# Valdis.net
KiCad netlist of a schematic drawn in Altium Designer
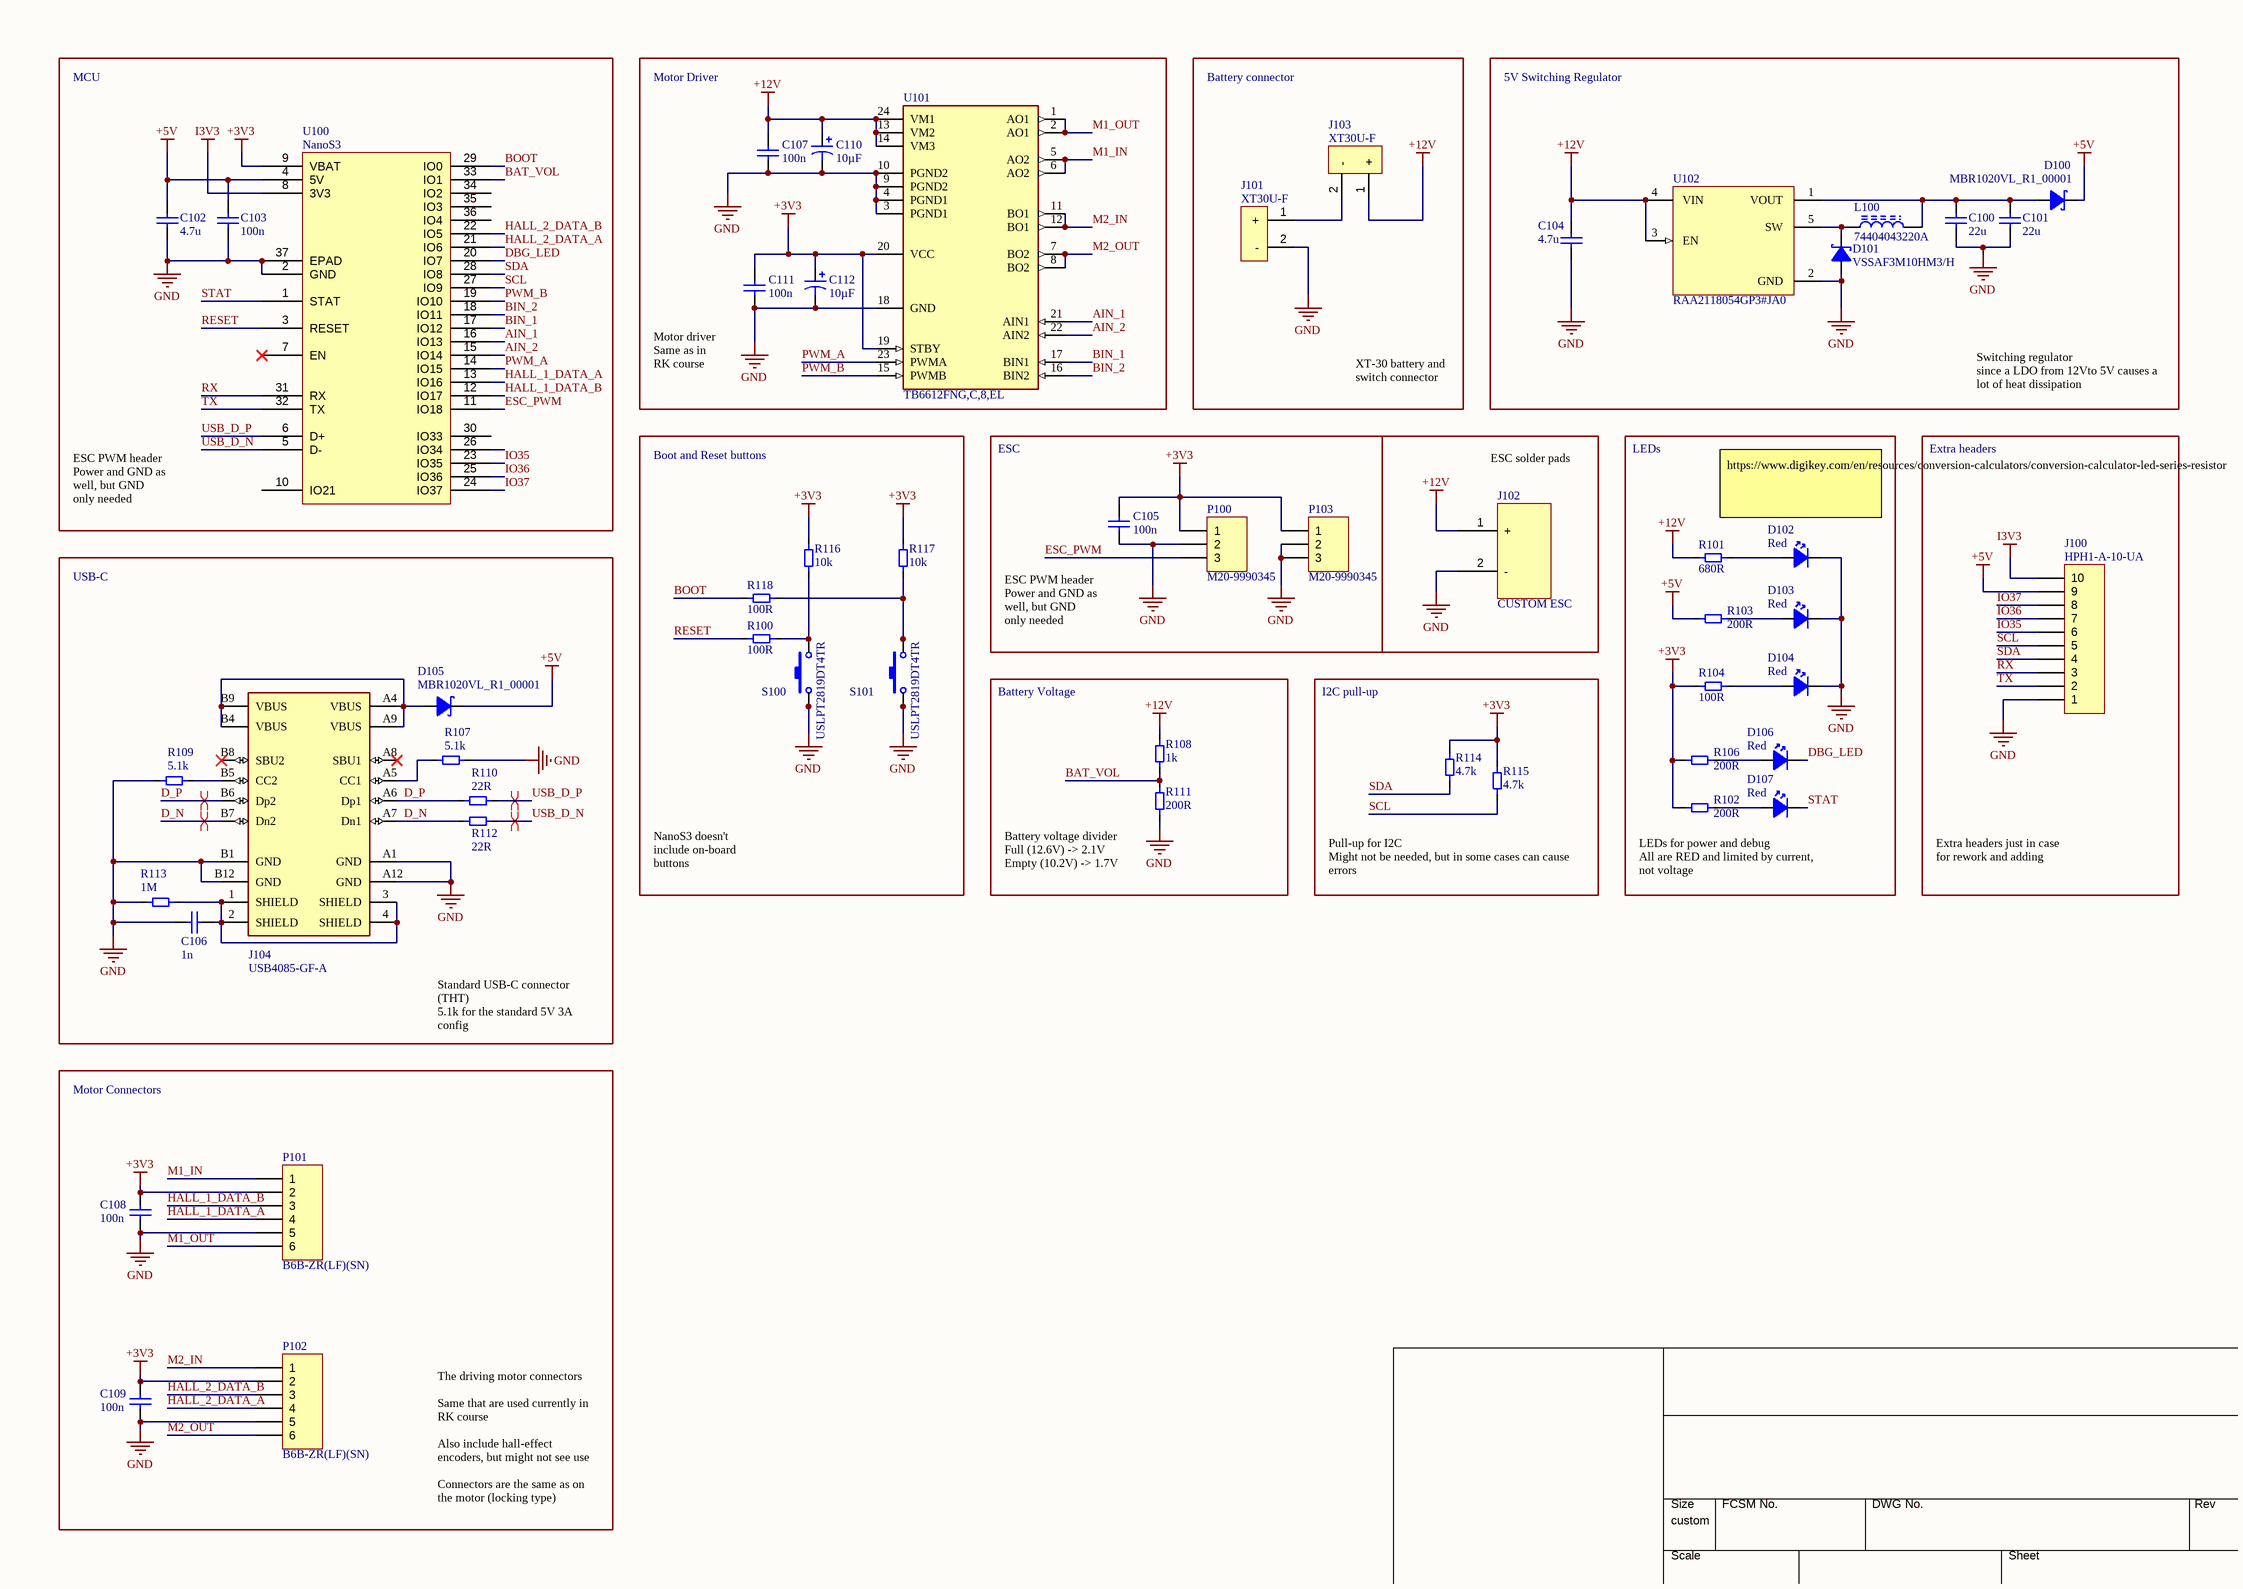
[diagram p0: Valdis.SchDoc]

(export (version "E")
  (design (tool "Eeschema 10.0.6"))
  (components
    (comp (ref "C100")
      (value "22u")
      (footprint "MLCC_1206_M")
      (description "MLCC, 1206, 22u, 10%, 16V, X5R")
      (fields (field (name "MANUFACTURER") "Any") (field (name "VOLTAGE") "16V"))
      (libsource (lib "Krakul Vault") (part "CAPACITOR_NONPOL_IEC"))
    )
    (comp (ref "C101")
      (value "22u")
      (footprint "MLCC_1206_M")
      (description "MLCC, 1206, 22u, 10%, 16V, X5R")
      (fields (field (name "MANUFACTURER") "Any") (field (name "VOLTAGE") "16V"))
      (libsource (lib "Krakul Vault") (part "CAPACITOR_NONPOL_IEC"))
    )
    (comp (ref "C102")
      (value "4.7u")
      (footprint "MLCC_0805_M")
      (description "MLCC, 0805, 4.7u, 10%, 50V, X5R")
      (fields (field (name "MANUFACTURER") "Any") (field (name "VOLTAGE") "50V"))
      (libsource (lib "Krakul Vault") (part "CAPACITOR_NONPOL_IEC"))
    )
    (comp (ref "C103")
      (value "100n")
      (footprint "MLCC_0603_M")
      (description "MLCC, 0603, 100n, 10%, 35V, X7R")
      (fields (field (name "MANUFACTURER") "Any") (field (name "VOLTAGE") "35V"))
      (libsource (lib "Krakul Vault") (part "CAPACITOR_NONPOL_IEC"))
    )
    (comp (ref "C104")
      (value "4.7u")
      (footprint "MLCC_1206_M")
      (description "MLCC, 1206, 4.7u, 10%, 35V, X5R")
      (fields (field (name "VOLTAGE") "35V") (field (name "TOLERANCE") "10%"))
      (libsource (lib "Krakul Vault") (part "CAPACITOR_NONPOL_IEC"))
    )
    (comp (ref "C105")
      (value "100n")
      (footprint "MLCC_0603_M")
      (description "MLCC, 0603, 100n, 10%, 50V, X7R")
      (fields (field (name "VOLTAGE") "50V") (field (name "TOLERANCE") "10%"))
      (libsource (lib "Krakul Vault") (part "CAPACITOR_NONPOL_IEC"))
    )
    (comp (ref "C106")
      (value "1n")
      (footprint "MLCC_0603_M")
      (description "MLCC, 0603, 1n, 10%, 50V, X7R")
      (fields (field (name "MANUFACTURER") "Any") (field (name "VOLTAGE") "50V"))
      (libsource (lib "Krakul Vault") (part "CAPACITOR_NONPOL_IEC"))
    )
    (comp (ref "C107")
      (value "100n")
      (footprint "MLCC_0603_M")
      (description "MLCC, 0603, 100n, 10%, 50V, X7R")
      (fields (field (name "VOLTAGE") "50V") (field (name "TOLERANCE") "10%"))
      (libsource (lib "Krakul Vault") (part "CAPACITOR_NONPOL_IEC"))
    )
    (comp (ref "C108")
      (value "100n")
      (footprint "MLCC_0603_M")
      (description "MLCC, 0603, 100n, 10%, 35V, X7R")
      (fields (field (name "MANUFACTURER") "Any") (field (name "VOLTAGE") "35V"))
      (libsource (lib "Krakul Vault") (part "CAPACITOR_NONPOL_IEC"))
    )
    (comp (ref "C109")
      (value "100n")
      (footprint "MLCC_0603_M")
      (description "MLCC, 0603, 100n, 10%, 35V, X7R")
      (fields (field (name "MANUFACTURER") "Any") (field (name "VOLTAGE") "35V"))
      (libsource (lib "Krakul Vault") (part "CAPACITOR_NONPOL_IEC"))
    )
    (comp (ref "C110")
      (value "10µF")
      (footprint "593D106X9025C2TE3-Footprint-1")
      (description "10UF Solid MNO2 Tantalum Electrolytic Capacitor, 25 V DC +/-10%, T495 Series")
      (fields (field (name "MANUFACTURER") "Any") (field (name "PART NUMBER") "T495B106K025ATE750"))
      (libsource (lib "Krakul Vault") (part "GENERIC ELECTROLYTIC CAP"))
    )
    (comp (ref "C111")
      (value "100n")
      (footprint "MLCC_0603_M")
      (description "MLCC, 0603, 100n, 10%, 50V, X7R")
      (fields (field (name "VOLTAGE") "50V") (field (name "TOLERANCE") "10%"))
      (libsource (lib "Krakul Vault") (part "CAPACITOR_NONPOL_IEC"))
    )
    (comp (ref "C112")
      (value "10µF")
      (footprint "593D106X9025C2TE3-Footprint-1")
      (description "10UF Solid MNO2 Tantalum Electrolytic Capacitor, 25 V DC +/-10%, T495 Series")
      (fields (field (name "MANUFACTURER") "Any") (field (name "PART NUMBER") "T495B106K025ATE750"))
      (libsource (lib "Krakul Vault") (part "GENERIC ELECTROLYTIC CAP"))
    )
    (comp (ref "D100")
      (value "MBR1020VL_R1_00001")
      (footprint "FP-MBR1020VL_R1_00001-MFG")
      (description "Rectifier Diode, Schottky, 1 Phase, 1 Element, 1A, 20V V(RRM), Silicon")
      (fields (field (name "MANUFACTURER") "Panjit"))
      (libsource (lib "Krakul Vault") (part "Schottky generic 2 pins"))
    )
    (comp (ref "D101")
      (value "VSSAF3M10HM3/H")
      (footprint "VSSAF3M10HM3_H-Footprint-1")
      (description "Rectifier Diode, Schottky, 1 Phase, 1 Element, 2.3A, 100V V(RRM), Silicon, DO-221AC")
      (libsource (lib "Krakul Vault") (part "Schottky generic 2 pins"))
    )
    (comp (ref "D102")
      (value "Red")
      (footprint "0603 RED LED")
      (description "Generic red 0603 LED")
      (fields (field (name "PART NUMBER") "Any Red 0603 LED") (field (name "MANUFACTURER") "Any"))
      (libsource (lib "Krakul Vault") (part "LED generic"))
    )
    (comp (ref "D103")
      (value "Red")
      (footprint "0603 RED LED")
      (description "Generic red 0603 LED")
      (fields (field (name "PART NUMBER") "Any Red 0603 LED") (field (name "MANUFACTURER") "Any"))
      (libsource (lib "Krakul Vault") (part "LED generic"))
    )
    (comp (ref "D104")
      (value "Red")
      (footprint "0603 RED LED")
      (description "Generic red 0603 LED")
      (fields (field (name "PART NUMBER") "Any Red 0603 LED") (field (name "MANUFACTURER") "Any"))
      (libsource (lib "Krakul Vault") (part "LED generic"))
    )
    (comp (ref "D105")
      (value "MBR1020VL_R1_00001")
      (footprint "FP-MBR1020VL_R1_00001-MFG")
      (description "Rectifier Diode, Schottky, 1 Phase, 1 Element, 1A, 20V V(RRM), Silicon")
      (fields (field (name "MANUFACTURER") "Panjit"))
      (libsource (lib "Krakul Vault") (part "Schottky generic 2 pins"))
    )
    (comp (ref "D106")
      (value "Red")
      (footprint "0603 RED LED")
      (description "Generic red 0603 LED")
      (fields (field (name "PART NUMBER") "Any Red 0603 LED") (field (name "MANUFACTURER") "Any"))
      (libsource (lib "Krakul Vault") (part "LED generic"))
    )
    (comp (ref "D107")
      (value "Red")
      (footprint "0603 RED LED")
      (description "Generic red 0603 LED")
      (fields (field (name "PART NUMBER") "Any Red 0603 LED") (field (name "MANUFACTURER") "Any"))
      (libsource (lib "Krakul Vault") (part "LED generic"))
    )
    (comp (ref "J100")
      (value "HPH1-A-10-UA")
      (footprint "HPH1-A-10-UA")
      (description "Conn Unshrouded Header HDR 10 POS 1.27mm Solder ST Top Entry Thru-Hole")
      (fields (field (name "MANUFACTURER") "Adam Tech"))
      (libsource (lib "Krakul Vault") (part "Header_Male_1R_10P"))
    )
    (comp (ref "J101")
      (value "XT30U-F")
      (footprint "XT30U-F")
      (description "Power Connector")
      (fields (field (name "MANUFACTURER") "AMASS"))
      (libsource (lib "Krakul Vault") (part "XT30U-F-Symbol-1"))
    )
    (comp (ref "J102")
      (value "CUSTOM ESC")
      (footprint "CUSTOM ESC-Footprint-1")
      (description "Custom ESC pinout")
      (fields (field (name "MANUFACTURER") "None"))
      (libsource (lib "Krakul Vault") (part "CUSTOM ESC"))
    )
    (comp (ref "J103")
      (value "XT30U-F")
      (footprint "XT30U-F")
      (description "Power Connector")
      (fields (field (name "MANUFACTURER") "AMASS"))
      (libsource (lib "") (part "XT30U-F-Symbol-1_1"))
    )
    (comp (ref "J104")
      (value "USB4085-GF-A")
      (footprint "FP-USB4085-GF-A-MFG")
      (description "USB Connector, 16 Contact(s), Female, Right Angle, Solder Terminal, Locking, Receptacle")
      (fields (field (name "MANUFACTURER") "GCT") (field (name "PART NUMBER") "USB4800-03-A"))
      (libsource (lib "Krakul Vault") (part "USB4085-GF-A"))
    )
    (comp (ref "L100")
      (value "74404043220A")
      (footprint "WE-LQS_4025")
      (description "General Purpose Inductor, 22uH, 20%, 1 Element, Nickel-zinc Ferrite-Core, SMD, 1616")
      (fields (field (name "MANUFACTURER") "Wurth Elektronik"))
      (libsource (lib "Krakul Vault") (part "INDUCTOR_SHIELDED"))
    )
    (comp (ref "P100")
      (value "M20-9990345")
      (footprint "3Pos Pin Header")
      (description "Connector Header Through Hole 3 position 0.100\" (2.54mm)")
      (fields (field (name "MANUFACTURER") "Harwin Inc."))
      (libsource (lib "Krakul Vault") (part "3 pin header"))
    )
    (comp (ref "P101")
      (value "B6B-ZR(LF)(SN)")
      (footprint "FP-B6B-ZR-SM4-TF_LF_SN-MFG")
      (description "Header for PCB; pitch 1.50mm; 6-contacts; THT; male; top entry; 50V/1A")
      (fields (field (name "MANUFACTURER") "JST Sales America Inc.") (field (name "PART NUMBER") "B6B-ZR"))
      (libsource (lib "Krakul Vault") (part "6 pin header"))
    )
    (comp (ref "P102")
      (value "B6B-ZR(LF)(SN)")
      (footprint "FP-B6B-ZR-SM4-TF_LF_SN-MFG")
      (description "Header for PCB; pitch 1.50mm; 6-contacts; THT; male; top entry; 50V/1A")
      (fields (field (name "MANUFACTURER") "JST Sales America Inc.") (field (name "PART NUMBER") "B6B-ZR"))
      (libsource (lib "Krakul Vault") (part "6 pin header"))
    )
    (comp (ref "P103")
      (value "M20-9990345")
      (footprint "3Pos Pin Header")
      (description "Connector Header Through Hole 3 position 0.100\" (2.54mm)")
      (fields (field (name "MANUFACTURER") "Harwin Inc."))
      (libsource (lib "Krakul Vault") (part "3 pin header"))
    )
    (comp (ref "R100")
      (value "100R")
      (footprint "Resistor_0603_M")
      (description "Resistor, 0603, 100R, 1%, 1/10W")
      (fields (field (name "POWER") "100mW") (field (name "MANUFACTURER") "Any"))
      (libsource (lib "Krakul Vault") (part "RESISTOR_GENERIC_IEC"))
    )
    (comp (ref "R101")
      (value "680R")
      (footprint "Resistor_0603_M")
      (description "Resistor, 0603, 680R, 1%, 1/10W")
      (fields (field (name "POWER") "100mW") (field (name "TOLERANCE") "1%"))
      (libsource (lib "Krakul Vault") (part "RESISTOR_GENERIC_IEC"))
    )
    (comp (ref "R102")
      (value "200R")
      (footprint "Resistor_0603_M")
      (description "Resistor, 0603, 200R, 1%, 1/10W")
      (fields (field (name "TOLERANCE") "1%") (field (name "POWER") "100mW"))
      (libsource (lib "Krakul Vault") (part "RESISTOR_GENERIC_IEC"))
    )
    (comp (ref "R103")
      (value "200R")
      (footprint "Resistor_0603_M")
      (description "Resistor, 0603, 200R, 1%, 1/10W")
      (fields (field (name "TOLERANCE") "1%") (field (name "POWER") "100mW"))
      (libsource (lib "Krakul Vault") (part "RESISTOR_GENERIC_IEC"))
    )
    (comp (ref "R104")
      (value "100R")
      (footprint "Resistor_0603_M")
      (description "Resistor, 0603, 100R, ≤5%, ≥1/16W")
      (fields (field (name "MANUFACTURER") "Any"))
      (libsource (lib "Krakul Vault") (part "RESISTOR_GENERIC_IEC"))
    )
    (comp (ref "R106")
      (value "200R")
      (footprint "Resistor_0603_M")
      (description "Resistor, 0603, 200R, 1%, 1/10W")
      (fields (field (name "TOLERANCE") "1%") (field (name "POWER") "100mW"))
      (libsource (lib "Krakul Vault") (part "RESISTOR_GENERIC_IEC"))
    )
    (comp (ref "R107")
      (value "5.1k")
      (footprint "Resistor_0603_M")
      (description "Resistor, 0603, 5.1k, 1%, 1/10W")
      (fields (field (name "POWER") "100mW") (field (name "MANUFACTURER") "Any"))
      (libsource (lib "Krakul Vault") (part "RESISTOR_GENERIC_IEC"))
    )
    (comp (ref "R108")
      (value "1k")
      (footprint "Resistor_0603_M")
      (description "Resistor, 0603, 1k, 0.1%, 1/16W")
      (fields (field (name "MANUFACTURER") "Any"))
      (libsource (lib "Krakul Vault") (part "RESISTOR_GENERIC_IEC"))
    )
    (comp (ref "R109")
      (value "5.1k")
      (footprint "Resistor_0603_M")
      (description "Resistor, 0603, 5.1k, 1%, 1/10W")
      (fields (field (name "POWER") "100mW") (field (name "MANUFACTURER") "Any"))
      (libsource (lib "Krakul Vault") (part "RESISTOR_GENERIC_IEC"))
    )
    (comp (ref "R110")
      (value "22R")
      (footprint "Resistor_0603_M")
      (description "Resistor, 0603, 22R, 1%, 1/10W")
      (fields (field (name "TOLERANCE") "1%") (field (name "MANUFACTURER") "Any"))
      (libsource (lib "Krakul Vault") (part "RESISTOR_GENERIC_IEC"))
    )
    (comp (ref "R111")
      (value "200R")
      (footprint "Resistor_0603_M")
      (description "Resistor, 0603, 220R, 1%, 1/10W")
      (fields (field (name "TOLERANCE") "1%") (field (name "MANUFACTURER") "Any"))
      (libsource (lib "Krakul Vault") (part "RESISTOR_GENERIC_IEC"))
    )
    (comp (ref "R112")
      (value "22R")
      (footprint "Resistor_0603_M")
      (description "Resistor, 0603, 22R, 1%, 1/10W")
      (fields (field (name "TOLERANCE") "1%") (field (name "MANUFACTURER") "Any"))
      (libsource (lib "Krakul Vault") (part "RESISTOR_GENERIC_IEC"))
    )
    (comp (ref "R113")
      (value "1M")
      (footprint "Resistor_1206_M")
      (description "Resistor, 1206, 1M, 1%, 1/4W")
      (fields (field (name "MANUFACTURER") "Any"))
      (libsource (lib "Krakul Vault") (part "RESISTOR_GENERIC_IEC"))
    )
    (comp (ref "R114")
      (value "4.7k")
      (footprint "Resistor_0603_M")
      (description "Resistor, 0603, 4.7k, 1%, 1/10W")
      (fields (field (name "MANUFACTURER") "Any") (field (name "POWER") "100mW"))
      (libsource (lib "Krakul Vault") (part "RESISTOR_GENERIC_IEC"))
    )
    (comp (ref "R115")
      (value "4.7k")
      (footprint "Resistor_0603_M")
      (description "Resistor, 0603, 4.7k, 1%, 1/10W")
      (fields (field (name "MANUFACTURER") "Any") (field (name "POWER") "100mW"))
      (libsource (lib "Krakul Vault") (part "RESISTOR_GENERIC_IEC"))
    )
    (comp (ref "R116")
      (value "10k")
      (footprint "Resistor_0603_M")
      (description "Resistor, 0603, 10k, 1%, 1/10W")
      (fields (field (name "MANUFACTURER") "Any") (field (name "TOLERANCE") "1%"))
      (libsource (lib "Krakul Vault") (part "RESISTOR_GENERIC_IEC"))
    )
    (comp (ref "R117")
      (value "10k")
      (footprint "Resistor_0603_M")
      (description "Resistor, 0603, 10k, 1%, 1/10W")
      (fields (field (name "MANUFACTURER") "Any") (field (name "TOLERANCE") "1%"))
      (libsource (lib "Krakul Vault") (part "RESISTOR_GENERIC_IEC"))
    )
    (comp (ref "R118")
      (value "100R")
      (footprint "Resistor_0603_M")
      (description "Resistor, 0603, 100R, 1%, 1/10W")
      (fields (field (name "POWER") "100mW") (field (name "MANUFACTURER") "Any"))
      (libsource (lib "Krakul Vault") (part "RESISTOR_GENERIC_IEC"))
    )
    (comp (ref "S100")
      (value "USLPT2819DT4TR")
      (footprint "USLPT2819DT4TR-Footprint-1")
      (description "Keypad Switch, SPST, 0.05A, 1.96N, Solder Terminal, Panel Mount")
      (fields (field (name "MANUFACTURER") "TE Connectivity ALCOSWITCH Switches"))
      (libsource (lib "Krakul Vault") (part "Copy of Switch 4-pin"))
    )
    (comp (ref "S101")
      (value "USLPT2819DT4TR")
      (footprint "USLPT2819DT4TR-Footprint-1")
      (description "Keypad Switch, SPST, 0.05A, 1.96N, Solder Terminal, Panel Mount")
      (fields (field (name "MANUFACTURER") "TE Connectivity ALCOSWITCH Switches"))
      (libsource (lib "Krakul Vault") (part "Copy of Switch 4-pin"))
    )
    (comp (ref "U100")
      (value "NanoS3")
      (footprint "NanoS3")
      (description "Unexpected Maker's NanoS3 DevKit")
      (fields (field (name "MANUFACTURER") "Unexpected Maker"))
      (libsource (lib "Krakul Vault") (part "NanoS3"))
    )
    (comp (ref "U101")
      (value "TB6612FNG,C,8,EL")
      (footprint "FP-SSOP24-P-300-0_65A-MFG")
      (description "DC Motor Driver 2.7V to 5.5V 24-Pin SSOP Embossed T/R")
      (fields (field (name "MANUFACTURER") "Toshiba") (field (name "PART NUMBER") "TBG6612FNG"))
      (libsource (lib "Krakul Vault") (part "TBG6612FNG"))
    )
    (comp (ref "U102")
      (value "RAA2118054GP3#JA0")
      (footprint "P5_064B_MFG")
      (description "Switching Regulator, Current-mode, 0.3A, 230kHz Switching Freq-Max, PDSO5")
      (fields (field (name "MANUFACTURER") "Renesas / Intersil"))
      (libsource (lib "Krakul Vault") (part "04ef17e7ed04f306c00cc4b237f44d7"))
    )
  )
  (nets
    (net (code "1") (name "+3V3") (class "Default")
      (node (ref "C105") (pin "1") (pinfunction "1_1") (pintype "passive"))
      (node (ref "C108") (pin "2") (pinfunction "2_2") (pintype "passive"))
      (node (ref "C109") (pin "2") (pinfunction "2_2") (pintype "passive"))
      (node (ref "C111") (pin "1") (pinfunction "1_1") (pintype "passive"))
      (node (ref "C112") (pin "2") (pinfunction "2_2") (pintype "passive"))
      (node (ref "P100") (pin "1") (pinfunction "1_1") (pintype "passive"))
      (node (ref "P101") (pin "2") (pinfunction "2_2") (pintype "passive"))
      (node (ref "P102") (pin "2") (pinfunction "2_2") (pintype "passive"))
      (node (ref "P103") (pin "1") (pinfunction "1_1") (pintype "passive"))
      (node (ref "R102") (pin "1") (pinfunction "1_1") (pintype "passive"))
      (node (ref "R104") (pin "1") (pinfunction "1_1") (pintype "passive"))
      (node (ref "R106") (pin "1") (pinfunction "1_1") (pintype "passive"))
      (node (ref "R114") (pin "2") (pinfunction "2_2") (pintype "passive"))
      (node (ref "R115") (pin "2") (pinfunction "2_2") (pintype "passive"))
      (node (ref "R116") (pin "2") (pinfunction "2_2") (pintype "passive"))
      (node (ref "R117") (pin "2") (pinfunction "2_2") (pintype "passive"))
      (node (ref "U100") (pin "9") (pinfunction "VBAT_9") (pintype "passive"))
      (node (ref "U101") (pin "19") (pinfunction "STBY_19") (pintype "input"))
      (node (ref "U101") (pin "20") (pinfunction "VCC_20") (pintype "power_in"))
    )
    (net (code "2") (name "+5V") (class "Default")
      (node (ref "C102") (pin "2") (pinfunction "2_2") (pintype "passive"))
      (node (ref "C103") (pin "2") (pinfunction "2_2") (pintype "passive"))
      (node (ref "D100") (pin "1") (pinfunction "C_1") (pintype "passive"))
      (node (ref "D105") (pin "1") (pinfunction "C_1") (pintype "passive"))
      (node (ref "J100") (pin "9") (pinfunction "9_9") (pintype "passive"))
      (node (ref "R103") (pin "1") (pinfunction "1_1") (pintype "passive"))
      (node (ref "U100") (pin "4") (pinfunction "5V_4") (pintype "passive"))
    )
    (net (code "3") (name "+12V") (class "Default")
      (node (ref "C104") (pin "2") (pinfunction "2_2") (pintype "passive"))
      (node (ref "C107") (pin "1") (pinfunction "1_1") (pintype "passive"))
      (node (ref "C110") (pin "2") (pinfunction "2_2") (pintype "passive"))
      (node (ref "J102") (pin "1") (pinfunction "+_1") (pintype "passive"))
      (node (ref "J103") (pin "1") (pinfunction "+_1") (pintype "passive"))
      (node (ref "R101") (pin "2") (pinfunction "2_2") (pintype "passive"))
      (node (ref "R108") (pin "2") (pinfunction "2_2") (pintype "passive"))
      (node (ref "U101") (pin "13") (pinfunction "VM2_13") (pintype "power_in"))
      (node (ref "U101") (pin "14") (pinfunction "VM3_14") (pintype "power_in"))
      (node (ref "U101") (pin "24") (pinfunction "VM1_24") (pintype "power_in"))
      (node (ref "U102") (pin "3") (pinfunction "EN_3") (pintype "input"))
      (node (ref "U102") (pin "4") (pinfunction "VIN_4") (pintype "power_in"))
    )
    (net (code "4") (name "/AIN_1") (class "Default")
      (node (ref "U100") (pin "16") (pinfunction "IO13_16") (pintype "passive"))
      (node (ref "U101") (pin "21") (pinfunction "AIN1_21") (pintype "input"))
    )
    (net (code "5") (name "/AIN_2") (class "Default")
      (node (ref "U100") (pin "15") (pinfunction "IO14_15") (pintype "passive"))
      (node (ref "U101") (pin "22") (pinfunction "AIN2_22") (pintype "input"))
    )
    (net (code "6") (name "/BAT_VOL") (class "Default")
      (node (ref "R108") (pin "1") (pinfunction "1_1") (pintype "passive"))
      (node (ref "R111") (pin "2") (pinfunction "2_2") (pintype "passive"))
      (node (ref "U100") (pin "33") (pinfunction "IO1_33") (pintype "passive"))
    )
    (net (code "7") (name "/BIN_1") (class "Default")
      (node (ref "U100") (pin "17") (pinfunction "IO12_17") (pintype "passive"))
      (node (ref "U101") (pin "17") (pinfunction "BIN1_17") (pintype "input"))
    )
    (net (code "8") (name "/BIN_2") (class "Default")
      (node (ref "U100") (pin "18") (pinfunction "IO11_18") (pintype "passive"))
      (node (ref "U101") (pin "16") (pinfunction "BIN2_16") (pintype "input"))
    )
    (net (code "9") (name "/BOOT") (class "Default")
      (node (ref "R118") (pin "2") (pinfunction "2_2") (pintype "passive"))
      (node (ref "U100") (pin "29") (pinfunction "IO0_29") (pintype "passive"))
    )
    (net (code "10") (name "/DBG_LED") (class "Default")
      (node (ref "D106") (pin "1") (pinfunction "C_1") (pintype "passive"))
      (node (ref "U100") (pin "20") (pinfunction "IO7_20") (pintype "passive"))
    )
    (net (code "11") (name "/D_N") (class "Default")
      (node (ref "J104") (pin "A7") (pinfunction "Dn1_A7") (pintype "bidirectional"))
      (node (ref "J104") (pin "B7") (pinfunction "Dn2_B7") (pintype "bidirectional"))
      (node (ref "R112") (pin "1") (pinfunction "1_1") (pintype "passive"))
    )
    (net (code "12") (name "/D_P") (class "Default")
      (node (ref "J104") (pin "A6") (pinfunction "Dp1_A6") (pintype "bidirectional"))
      (node (ref "J104") (pin "B6") (pinfunction "Dp2_B6") (pintype "bidirectional"))
      (node (ref "R110") (pin "1") (pinfunction "1_1") (pintype "passive"))
    )
    (net (code "13") (name "/ESC_PWM") (class "Default")
      (node (ref "P100") (pin "3") (pinfunction "3_3") (pintype "passive"))
      (node (ref "U100") (pin "11") (pinfunction "IO18_11") (pintype "passive"))
    )
    (net (code "14") (name "/HALL_1_DATA_A") (class "Default")
      (node (ref "P101") (pin "4") (pinfunction "4_4") (pintype "passive"))
      (node (ref "U100") (pin "13") (pinfunction "IO16_13") (pintype "passive"))
    )
    (net (code "15") (name "/HALL_1_DATA_B") (class "Default")
      (node (ref "P101") (pin "3") (pinfunction "3_3") (pintype "passive"))
      (node (ref "U100") (pin "12") (pinfunction "IO17_12") (pintype "passive"))
    )
    (net (code "16") (name "/HALL_2_DATA_A") (class "Default")
      (node (ref "P102") (pin "4") (pinfunction "4_4") (pintype "passive"))
      (node (ref "U100") (pin "21") (pinfunction "IO6_21") (pintype "passive"))
    )
    (net (code "17") (name "/HALL_2_DATA_B") (class "Default")
      (node (ref "P102") (pin "3") (pinfunction "3_3") (pintype "passive"))
      (node (ref "U100") (pin "22") (pinfunction "IO5_22") (pintype "passive"))
    )
    (net (code "18") (name "/IO35") (class "Default")
      (node (ref "J100") (pin "6") (pinfunction "6_6") (pintype "passive"))
      (node (ref "U100") (pin "23") (pinfunction "IO35_23") (pintype "passive"))
    )
    (net (code "19") (name "/IO36") (class "Default")
      (node (ref "J100") (pin "7") (pinfunction "7_7") (pintype "passive"))
      (node (ref "U100") (pin "25") (pinfunction "IO36_25") (pintype "passive"))
    )
    (net (code "20") (name "/IO37") (class "Default")
      (node (ref "J100") (pin "8") (pinfunction "8_8") (pintype "passive"))
      (node (ref "U100") (pin "24") (pinfunction "IO37_24") (pintype "passive"))
    )
    (net (code "21") (name "/M1_IN") (class "Default")
      (node (ref "P101") (pin "1") (pinfunction "1_1") (pintype "passive"))
      (node (ref "U101") (pin "5") (pinfunction "AO2_5") (pintype "output"))
      (node (ref "U101") (pin "6") (pinfunction "AO2_6") (pintype "output"))
    )
    (net (code "22") (name "/M1_OUT") (class "Default")
      (node (ref "P101") (pin "6") (pinfunction "6_6") (pintype "passive"))
      (node (ref "U101") (pin "1") (pinfunction "AO1_1") (pintype "output"))
      (node (ref "U101") (pin "2") (pinfunction "AO1_2") (pintype "output"))
    )
    (net (code "23") (name "/M2_IN") (class "Default")
      (node (ref "P102") (pin "1") (pinfunction "1_1") (pintype "passive"))
      (node (ref "U101") (pin "11") (pinfunction "BO1_11") (pintype "output"))
      (node (ref "U101") (pin "12") (pinfunction "BO1_12") (pintype "output"))
    )
    (net (code "24") (name "/M2_OUT") (class "Default")
      (node (ref "P102") (pin "6") (pinfunction "6_6") (pintype "passive"))
      (node (ref "U101") (pin "7") (pinfunction "BO2_7") (pintype "output"))
      (node (ref "U101") (pin "8") (pinfunction "BO2_8") (pintype "output"))
    )
    (net (code "25") (name "/PWM_A") (class "Default")
      (node (ref "U100") (pin "14") (pinfunction "IO15_14") (pintype "passive"))
      (node (ref "U101") (pin "23") (pinfunction "PWMA_23") (pintype "input"))
    )
    (net (code "26") (name "/PWM_B") (class "Default")
      (node (ref "U100") (pin "19") (pinfunction "IO10_19") (pintype "passive"))
      (node (ref "U101") (pin "15") (pinfunction "PWMB_15") (pintype "input"))
    )
    (net (code "27") (name "/RESET") (class "Default")
      (node (ref "R100") (pin "2") (pinfunction "2_2") (pintype "passive"))
      (node (ref "U100") (pin "3") (pinfunction "RESET_3") (pintype "passive"))
    )
    (net (code "28") (name "/RX") (class "Default")
      (node (ref "J100") (pin "3") (pinfunction "3_3") (pintype "passive"))
      (node (ref "U100") (pin "31") (pinfunction "RX_31") (pintype "passive"))
    )
    (net (code "29") (name "/SCL") (class "Default")
      (node (ref "J100") (pin "5") (pinfunction "5_5") (pintype "passive"))
      (node (ref "R115") (pin "1") (pinfunction "1_1") (pintype "passive"))
      (node (ref "U100") (pin "27") (pinfunction "IO9_27") (pintype "passive"))
    )
    (net (code "30") (name "/SDA") (class "Default")
      (node (ref "J100") (pin "4") (pinfunction "4_4") (pintype "passive"))
      (node (ref "R114") (pin "1") (pinfunction "1_1") (pintype "passive"))
      (node (ref "U100") (pin "28") (pinfunction "IO8_28") (pintype "passive"))
    )
    (net (code "31") (name "/STAT") (class "Default")
      (node (ref "D107") (pin "1") (pinfunction "C_1") (pintype "passive"))
      (node (ref "U100") (pin "1") (pinfunction "STAT_1") (pintype "passive"))
    )
    (net (code "32") (name "/TX") (class "Default")
      (node (ref "J100") (pin "2") (pinfunction "2_2") (pintype "passive"))
      (node (ref "U100") (pin "32") (pinfunction "TX_32") (pintype "passive"))
    )
    (net (code "33") (name "/USB_D_N") (class "Default")
      (node (ref "R112") (pin "2") (pinfunction "2_2") (pintype "passive"))
      (node (ref "U100") (pin "5") (pinfunction "D-_5") (pintype "passive"))
    )
    (net (code "34") (name "/USB_D_P") (class "Default")
      (node (ref "R110") (pin "2") (pinfunction "2_2") (pintype "passive"))
      (node (ref "U100") (pin "6") (pinfunction "D+_6") (pintype "passive"))
    )
    (net (code "35") (name "GND") (class "Default")
      (node (ref "C100") (pin "1") (pinfunction "1_1") (pintype "passive"))
      (node (ref "C101") (pin "1") (pinfunction "1_1") (pintype "passive"))
      (node (ref "C102") (pin "1") (pinfunction "1_1") (pintype "passive"))
      (node (ref "C103") (pin "1") (pinfunction "1_1") (pintype "passive"))
      (node (ref "C104") (pin "1") (pinfunction "1_1") (pintype "passive"))
      (node (ref "C105") (pin "2") (pinfunction "2_2") (pintype "passive"))
      (node (ref "C106") (pin "2") (pinfunction "2_2") (pintype "passive"))
      (node (ref "C107") (pin "2") (pinfunction "2_2") (pintype "passive"))
      (node (ref "C108") (pin "1") (pinfunction "1_1") (pintype "passive"))
      (node (ref "C109") (pin "1") (pinfunction "1_1") (pintype "passive"))
      (node (ref "C110") (pin "1") (pinfunction "1_1") (pintype "passive"))
      (node (ref "C111") (pin "2") (pinfunction "2_2") (pintype "passive"))
      (node (ref "C112") (pin "1") (pinfunction "1_1") (pintype "passive"))
      (node (ref "D101") (pin "2") (pinfunction "A_2") (pintype "passive"))
      (node (ref "D102") (pin "1") (pinfunction "C_1") (pintype "passive"))
      (node (ref "D103") (pin "1") (pinfunction "C_1") (pintype "passive"))
      (node (ref "D104") (pin "1") (pinfunction "C_1") (pintype "passive"))
      (node (ref "J100") (pin "1") (pinfunction "1_1") (pintype "passive"))
      (node (ref "J101") (pin "2") (pinfunction "-_2") (pintype "passive"))
      (node (ref "J102") (pin "2") (pinfunction "-_2") (pintype "passive"))
      (node (ref "J104") (pin "A1") (pinfunction "GND_A1") (pintype "power_in"))
      (node (ref "J104") (pin "A12") (pinfunction "GND_A12") (pintype "power_in"))
      (node (ref "J104") (pin "B1") (pinfunction "GND_B1") (pintype "power_in"))
      (node (ref "J104") (pin "B12") (pinfunction "GND_B12") (pintype "power_in"))
      (node (ref "P100") (pin "2") (pinfunction "2_2") (pintype "passive"))
      (node (ref "P101") (pin "5") (pinfunction "5_5") (pintype "passive"))
      (node (ref "P102") (pin "5") (pinfunction "5_5") (pintype "passive"))
      (node (ref "P103") (pin "2") (pinfunction "2_2") (pintype "passive"))
      (node (ref "P103") (pin "3") (pinfunction "3_3") (pintype "passive"))
      (node (ref "R107") (pin "2") (pinfunction "2_2") (pintype "passive"))
      (node (ref "R109") (pin "1") (pinfunction "1_1") (pintype "passive"))
      (node (ref "R111") (pin "1") (pinfunction "1_1") (pintype "passive"))
      (node (ref "R113") (pin "2") (pinfunction "2_2") (pintype "passive"))
      (node (ref "S100") (pin "1") (pinfunction "1_1") (pintype "passive"))
      (node (ref "S100") (pin "2") (pinfunction "2_2") (pintype "passive"))
      (node (ref "S101") (pin "1") (pinfunction "1_1") (pintype "passive"))
      (node (ref "S101") (pin "2") (pinfunction "2_2") (pintype "passive"))
      (node (ref "U100") (pin "2") (pinfunction "GND_2") (pintype "passive"))
      (node (ref "U100") (pin "37") (pinfunction "EPAD_37") (pintype "passive"))
      (node (ref "U101") (pin "10") (pinfunction "PGND2_10") (pintype "power_in"))
      (node (ref "U101") (pin "18") (pinfunction "GND_18") (pintype "power_in"))
      (node (ref "U101") (pin "3") (pinfunction "PGND1_3") (pintype "power_in"))
      (node (ref "U101") (pin "4") (pinfunction "PGND1_4") (pintype "power_in"))
      (node (ref "U101") (pin "9") (pinfunction "PGND2_9") (pintype "power_in"))
      (node (ref "U102") (pin "2") (pinfunction "GND_2") (pintype "power_in"))
    )
    (net (code "36") (name "I3V3") (class "Default")
      (node (ref "J100") (pin "10") (pinfunction "10_10") (pintype "passive"))
      (node (ref "U100") (pin "8") (pinfunction "3V3_8") (pintype "passive"))
    )
    (net (code "37") (name "Net-(C106-Pad1)") (class "Default")
      (node (ref "C106") (pin "1") (pinfunction "1_1") (pintype "passive"))
      (node (ref "J104") (pin "1") (pinfunction "SHIELD_1") (pintype "passive"))
      (node (ref "J104") (pin "2") (pinfunction "SHIELD_2") (pintype "passive"))
      (node (ref "J104") (pin "3") (pinfunction "SHIELD_3") (pintype "passive"))
      (node (ref "J104") (pin "4") (pinfunction "SHIELD_4") (pintype "passive"))
      (node (ref "R113") (pin "1") (pinfunction "1_1") (pintype "passive"))
    )
    (net (code "38") (name "Net-(D100-A)") (class "Default")
      (node (ref "C100") (pin "2") (pinfunction "2_2") (pintype "passive"))
      (node (ref "C101") (pin "2") (pinfunction "2_2") (pintype "passive"))
      (node (ref "D100") (pin "2") (pinfunction "A_2") (pintype "passive"))
      (node (ref "L100") (pin "2") (pinfunction "2_2") (pintype "passive"))
      (node (ref "U102") (pin "1") (pinfunction "VOUT_1") (pintype "power_in"))
    )
    (net (code "39") (name "Net-(D101-C)") (class "Default")
      (node (ref "D101") (pin "1") (pinfunction "C_1") (pintype "passive"))
      (node (ref "L100") (pin "1") (pinfunction "1_1") (pintype "passive"))
      (node (ref "U102") (pin "5") (pinfunction "SW_5") (pintype "passive"))
    )
    (net (code "40") (name "Net-(D102-A)") (class "Default")
      (node (ref "D102") (pin "2") (pinfunction "A_2") (pintype "passive"))
      (node (ref "R101") (pin "1") (pinfunction "1_1") (pintype "passive"))
    )
    (net (code "41") (name "Net-(D103-A)") (class "Default")
      (node (ref "D103") (pin "2") (pinfunction "A_2") (pintype "passive"))
      (node (ref "R103") (pin "2") (pinfunction "2_2") (pintype "passive"))
    )
    (net (code "42") (name "Net-(D104-A)") (class "Default")
      (node (ref "D104") (pin "2") (pinfunction "A_2") (pintype "passive"))
      (node (ref "R104") (pin "2") (pinfunction "2_2") (pintype "passive"))
    )
    (net (code "43") (name "Net-(D105-A)") (class "Default")
      (node (ref "D105") (pin "2") (pinfunction "A_2") (pintype "passive"))
      (node (ref "J104") (pin "A4") (pinfunction "VBUS_A4") (pintype "power_in"))
      (node (ref "J104") (pin "A9") (pinfunction "VBUS_A9") (pintype "power_in"))
      (node (ref "J104") (pin "B4") (pinfunction "VBUS_B4") (pintype "power_in"))
      (node (ref "J104") (pin "B9") (pinfunction "VBUS_B9") (pintype "power_in"))
    )
    (net (code "44") (name "Net-(D106-A)") (class "Default")
      (node (ref "D106") (pin "2") (pinfunction "A_2") (pintype "passive"))
      (node (ref "R106") (pin "2") (pinfunction "2_2") (pintype "passive"))
    )
    (net (code "45") (name "Net-(D107-A)") (class "Default")
      (node (ref "D107") (pin "2") (pinfunction "A_2") (pintype "passive"))
      (node (ref "R102") (pin "2") (pinfunction "2_2") (pintype "passive"))
    )
    (net (code "46") (name "Net-(J101-+)") (class "Default")
      (node (ref "J101") (pin "1") (pinfunction "+_1") (pintype "passive"))
      (node (ref "J103") (pin "2") (pinfunction "-_2") (pintype "passive"))
    )
    (net (code "47") (name "Net-(J104-CC1)") (class "Default")
      (node (ref "J104") (pin "A5") (pinfunction "CC1_A5") (pintype "bidirectional"))
      (node (ref "R107") (pin "1") (pinfunction "1_1") (pintype "passive"))
    )
    (net (code "48") (name "Net-(J104-CC2)") (class "Default")
      (node (ref "J104") (pin "B5") (pinfunction "CC2_B5") (pintype "bidirectional"))
      (node (ref "R109") (pin "2") (pinfunction "2_2") (pintype "passive"))
    )
    (net (code "49") (name "Net-(R100-Pad1)") (class "Default")
      (node (ref "R100") (pin "1") (pinfunction "1_1") (pintype "passive"))
      (node (ref "R116") (pin "1") (pinfunction "1_1") (pintype "passive"))
      (node (ref "S100") (pin "3") (pinfunction "3_3") (pintype "passive"))
      (node (ref "S100") (pin "4") (pinfunction "4_4") (pintype "passive"))
    )
    (net (code "50") (name "Net-(R117-Pad1)") (class "Default")
      (node (ref "R117") (pin "1") (pinfunction "1_1") (pintype "passive"))
      (node (ref "R118") (pin "1") (pinfunction "1_1") (pintype "passive"))
      (node (ref "S101") (pin "3") (pinfunction "3_3") (pintype "passive"))
      (node (ref "S101") (pin "4") (pinfunction "4_4") (pintype "passive"))
    )
    (net (code "51") (name "unconnected-(J104-SBU1-PadA8)") (class "Default")
      (node (ref "J104") (pin "A8") (pinfunction "SBU1_A8") (pintype "bidirectional+no_connect"))
    )
    (net (code "52") (name "unconnected-(J104-SBU2-PadB8)") (class "Default")
      (node (ref "J104") (pin "B8") (pinfunction "SBU2_B8") (pintype "bidirectional+no_connect"))
    )
    (net (code "53") (name "unconnected-(U100-EN-Pad7)") (class "Default")
      (node (ref "U100") (pin "7") (pinfunction "EN_7") (pintype "passive+no_connect"))
    )
    (net (code "54") (name "unconnected-(U100-IO2-Pad34)") (class "Default")
      (node (ref "U100") (pin "34") (pinfunction "IO2_34") (pintype "passive"))
    )
    (net (code "55") (name "unconnected-(U100-IO3-Pad35)") (class "Default")
      (node (ref "U100") (pin "35") (pinfunction "IO3_35") (pintype "passive"))
    )
    (net (code "56") (name "unconnected-(U100-IO4-Pad36)") (class "Default")
      (node (ref "U100") (pin "36") (pinfunction "IO4_36") (pintype "passive"))
    )
    (net (code "57") (name "unconnected-(U100-IO21-Pad10)") (class "Default")
      (node (ref "U100") (pin "10") (pinfunction "IO21_10") (pintype "passive"))
    )
    (net (code "58") (name "unconnected-(U100-IO33-Pad30)") (class "Default")
      (node (ref "U100") (pin "30") (pinfunction "IO33_30") (pintype "passive"))
    )
    (net (code "59") (name "unconnected-(U100-IO34-Pad26)") (class "Default")
      (node (ref "U100") (pin "26") (pinfunction "IO34_26") (pintype "passive"))
    )
  )
)
